# CANdiy-Shield_v12.net
KiCad netlist of a schematic drawn in EAGLE
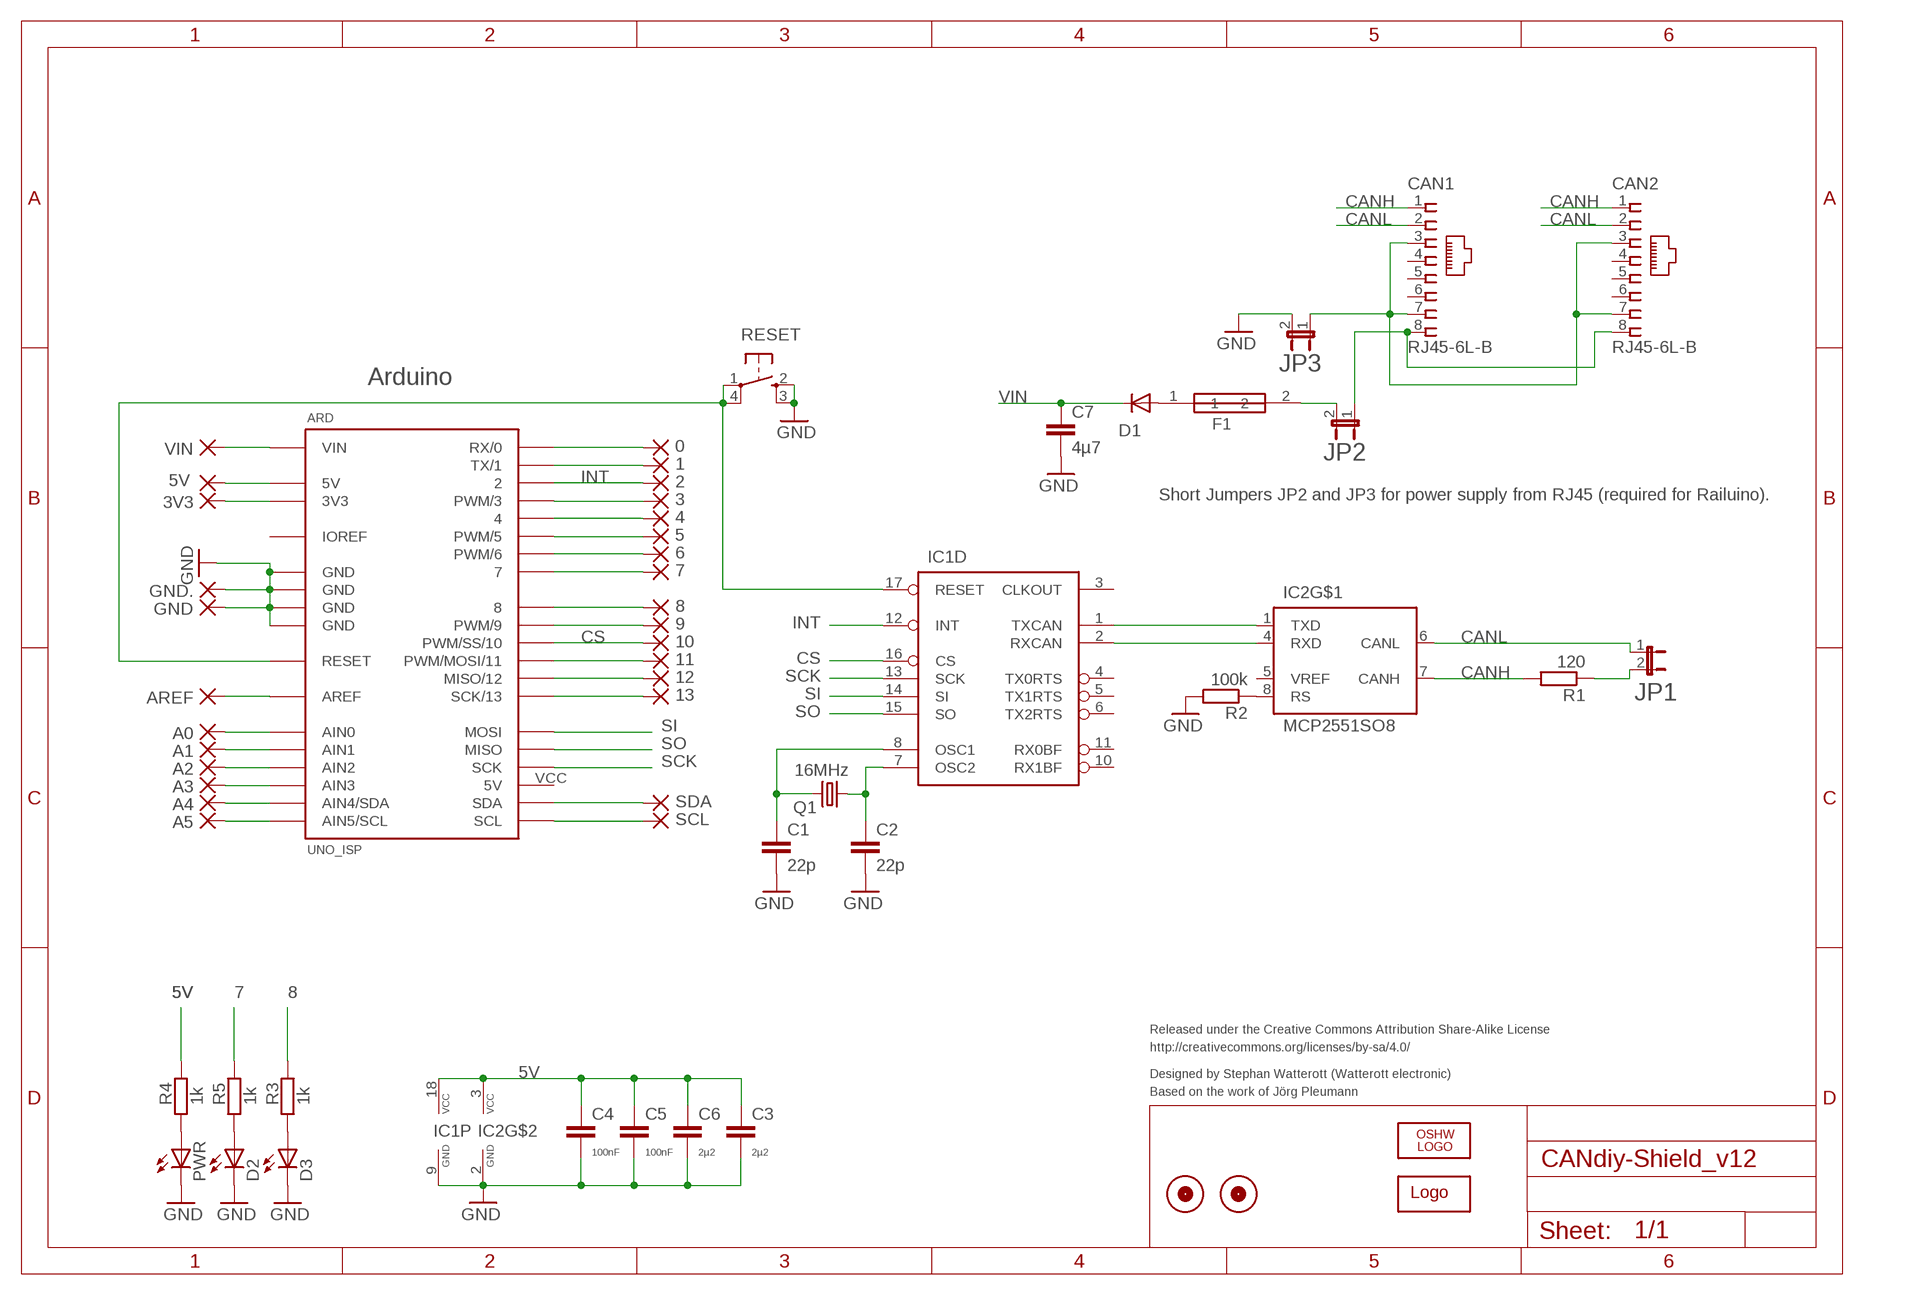
[diagram p0: schematic, sheet 1]

(export (version "E")
  (design (tool "Eeschema 10.0.6"))
  (components
    (comp (ref "0")
      (value "1,6/0,8")
      (footprint "eagle-import:1,6_0,8")
      (libsource (lib "eagle-import") (part "1,6/0,8"))
    )
    (comp (ref "1")
      (value "1,6/0,8")
      (footprint "eagle-import:1,6_0,8")
      (libsource (lib "eagle-import") (part "1,6/0,8"))
    )
    (comp (ref "2")
      (value "1,6/0,8")
      (footprint "eagle-import:1,6_0,8")
      (libsource (lib "eagle-import") (part "1,6/0,8"))
    )
    (comp (ref "3")
      (value "1,6/0,8")
      (footprint "eagle-import:1,6_0,8")
      (libsource (lib "eagle-import") (part "1,6/0,8"))
    )
    (comp (ref "3V3")
      (value "1,6/0,8")
      (footprint "eagle-import:1,6_0,8")
      (libsource (lib "eagle-import") (part "1,6/0,8"))
    )
    (comp (ref "4")
      (value "1,6/0,8")
      (footprint "eagle-import:1,6_0,8")
      (libsource (lib "eagle-import") (part "1,6/0,8"))
    )
    (comp (ref "5")
      (value "1,6/0,8")
      (footprint "eagle-import:1,6_0,8")
      (libsource (lib "eagle-import") (part "1,6/0,8"))
    )
    (comp (ref "5V")
      (value "1,6/0,8")
      (footprint "eagle-import:1,6_0,8")
      (libsource (lib "eagle-import") (part "1,6/0,8"))
    )
    (comp (ref "6")
      (value "1,6/0,8")
      (footprint "eagle-import:1,6_0,8")
      (libsource (lib "eagle-import") (part "1,6/0,8"))
    )
    (comp (ref "7")
      (value "1,6/0,8")
      (footprint "eagle-import:1,6_0,8")
      (libsource (lib "eagle-import") (part "1,6/0,8"))
    )
    (comp (ref "8")
      (value "1,6/0,8")
      (footprint "eagle-import:1,6_0,8")
      (libsource (lib "eagle-import") (part "1,6/0,8"))
    )
    (comp (ref "9")
      (value "1,6/0,8")
      (footprint "eagle-import:1,6_0,8")
      (libsource (lib "eagle-import") (part "1,6/0,8"))
    )
    (comp (ref "10")
      (value "1,6/0,8")
      (footprint "eagle-import:1,6_0,8")
      (libsource (lib "eagle-import") (part "1,6/0,8"))
    )
    (comp (ref "11")
      (value "1,6/0,8")
      (footprint "eagle-import:1,6_0,8")
      (libsource (lib "eagle-import") (part "1,6/0,8"))
    )
    (comp (ref "12")
      (value "1,6/0,8")
      (footprint "eagle-import:1,6_0,8")
      (libsource (lib "eagle-import") (part "1,6/0,8"))
    )
    (comp (ref "13")
      (value "1,6/0,8")
      (footprint "eagle-import:1,6_0,8")
      (libsource (lib "eagle-import") (part "1,6/0,8"))
    )
    (comp (ref "A0")
      (value "1,6/0,8")
      (footprint "eagle-import:1,6_0,8")
      (libsource (lib "eagle-import") (part "1,6/0,8"))
    )
    (comp (ref "A1")
      (value "1,6/0,8")
      (footprint "eagle-import:1,6_0,8")
      (libsource (lib "eagle-import") (part "1,6/0,8"))
    )
    (comp (ref "A2")
      (value "1,6/0,8")
      (footprint "eagle-import:1,6_0,8")
      (libsource (lib "eagle-import") (part "1,6/0,8"))
    )
    (comp (ref "A3")
      (value "1,6/0,8")
      (footprint "eagle-import:1,6_0,8")
      (libsource (lib "eagle-import") (part "1,6/0,8"))
    )
    (comp (ref "A4")
      (value "1,6/0,8")
      (footprint "eagle-import:1,6_0,8")
      (libsource (lib "eagle-import") (part "1,6/0,8"))
    )
    (comp (ref "A5")
      (value "1,6/0,8")
      (footprint "eagle-import:1,6_0,8")
      (libsource (lib "eagle-import") (part "1,6/0,8"))
    )
    (comp (ref "ARD")
      (value "UNO_ISP")
      (footprint "eagle-import:UNO_ISP")
      (libsource (lib "eagle-import") (part "UNO_ISP"))
    )
    (comp (ref "AREF")
      (value "1,6/0,8")
      (footprint "eagle-import:1,6_0,8")
      (libsource (lib "eagle-import") (part "1,6/0,8"))
    )
    (comp (ref "C1")
      (value "22p")
      (footprint "eagle-import:C0603")
      (libsource (lib "eagle-import") (part "C-EUC0603"))
    )
    (comp (ref "C2")
      (value "22p")
      (footprint "eagle-import:C0603")
      (libsource (lib "eagle-import") (part "C-EUC0603"))
    )
    (comp (ref "C3")
      (value "2µ2")
      (footprint "eagle-import:C0603")
      (libsource (lib "eagle-import") (part "C-EUC0603"))
    )
    (comp (ref "C4")
      (value "100nF")
      (footprint "eagle-import:C0603")
      (libsource (lib "eagle-import") (part "C-EUC0603"))
    )
    (comp (ref "C5")
      (value "100nF")
      (footprint "eagle-import:C0603")
      (libsource (lib "eagle-import") (part "C-EUC0603"))
    )
    (comp (ref "C6")
      (value "2µ2")
      (footprint "eagle-import:C0603")
      (libsource (lib "eagle-import") (part "C-EUC0603"))
    )
    (comp (ref "C7")
      (value "4µ7")
      (footprint "eagle-import:C1206")
      (libsource (lib "eagle-import") (part "C-EUC1206"))
    )
    (comp (ref "CAN1")
      (value "RJ45-6L-B")
      (footprint "eagle-import:RJ45-NO-SHIELD")
      (libsource (lib "eagle-import") (part "RJ45-6L-B"))
    )
    (comp (ref "CAN2")
      (value "RJ45-6L-B")
      (footprint "eagle-import:RJ45-NO-SHIELD")
      (libsource (lib "eagle-import") (part "RJ45-6L-B"))
    )
    (comp (ref "D1")
      (value "CGRM4001-G")
      (footprint "eagle-import:SOD-123_MINI-SMA")
      (libsource (lib "eagle-import") (part "CGRM400-G1"))
    )
    (comp (ref "D2")
      (value "LEDCHIPLED_0603")
      (footprint "eagle-import:CHIPLED_0603")
      (libsource (lib "eagle-import") (part "LEDCHIPLED_0603"))
    )
    (comp (ref "D3")
      (value "LEDCHIPLED_0603")
      (footprint "eagle-import:CHIPLED_0603")
      (libsource (lib "eagle-import") (part "LEDCHIPLED_0603"))
    )
    (comp (ref "F1")
      (value "F1")
      (footprint "eagle-import:L1812")
      (libsource (lib "eagle-import") (part "FUSE1812"))
    )
    (comp (ref "GND")
      (value "1,6/0,8")
      (footprint "eagle-import:1,6_0,8")
      (libsource (lib "eagle-import") (part "1,6/0,8"))
    )
    (comp (ref "GND.")
      (value "1,6/0,8")
      (footprint "eagle-import:1,6_0,8")
      (libsource (lib "eagle-import") (part "1,6/0,8"))
    )
    (comp (ref "IC1")
      (value "MCP2515SO")
      (footprint "eagle-import:SO-18W")
      (libsource (lib "eagle-import") (part "MCP2515SO"))
    )
    (comp (ref "IC2")
      (value "MCP2551SO8")
      (footprint "eagle-import:SO08")
      (libsource (lib "eagle-import") (part "MCP2551SO8"))
    )
    (comp (ref "JP1")
      (value "JP1E")
      (footprint "eagle-import:JP1")
      (libsource (lib "eagle-import") (part "JP1E"))
    )
    (comp (ref "JP2")
      (value "JP1E")
      (footprint "eagle-import:JP1")
      (libsource (lib "eagle-import") (part "JP1E"))
    )
    (comp (ref "JP3")
      (value "JP1E")
      (footprint "eagle-import:JP1")
      (libsource (lib "eagle-import") (part "JP1E"))
    )
    (comp (ref "LOGO2")
      (value "OSHW_LOGO_6MILX0100-NT")
      (footprint "eagle-import:OSHW_6X100_NOTEXT")
      (libsource (lib "eagle-import") (part "OSHW_LOGO_6MILX0100-NT"))
    )
    (comp (ref "PWR")
      (value "LEDCHIPLED_0603")
      (footprint "eagle-import:CHIPLED_0603")
      (libsource (lib "eagle-import") (part "LEDCHIPLED_0603"))
    )
    (comp (ref "Q1")
      (value "16MHz")
      (footprint "eagle-import:HC49UP")
      (libsource (lib "eagle-import") (part "CRYSTALHC49UP"))
    )
    (comp (ref "R1")
      (value "120")
      (footprint "eagle-import:R0603")
      (libsource (lib "eagle-import") (part "resistor_R-EU_R0603"))
    )
    (comp (ref "R2")
      (value "100k")
      (footprint "eagle-import:R0603")
      (libsource (lib "eagle-import") (part "resistor_R-EU_R0603"))
    )
    (comp (ref "R3")
      (value "1k")
      (footprint "eagle-import:R0603")
      (libsource (lib "eagle-import") (part "R-EU_R0603"))
    )
    (comp (ref "R4")
      (value "1k")
      (footprint "eagle-import:R0603")
      (libsource (lib "eagle-import") (part "R-EU_R0603"))
    )
    (comp (ref "R5")
      (value "1k")
      (footprint "eagle-import:R0603")
      (libsource (lib "eagle-import") (part "R-EU_R0603"))
    )
    (comp (ref "RESET")
      (value "SW_SMDS")
      (footprint "eagle-import:SW_SMD4")
      (libsource (lib "eagle-import") (part "SW_SMDS"))
    )
    (comp (ref "SCL")
      (value "1,6/0,8")
      (footprint "eagle-import:1,6_0,8")
      (libsource (lib "eagle-import") (part "1,6/0,8"))
    )
    (comp (ref "SDA")
      (value "1,6/0,8")
      (footprint "eagle-import:1,6_0,8")
      (libsource (lib "eagle-import") (part "1,6/0,8"))
    )
    (comp (ref "U$1")
      (value "WE-LOGO")
      (footprint "eagle-import:WE-LOGO")
      (libsource (lib "eagle-import") (part "WE-LOGO"))
    )
    (comp (ref "VIN")
      (value "1,6/0,8")
      (footprint "eagle-import:1,6_0,8")
      (libsource (lib "eagle-import") (part "1,6/0,8"))
    )
    (comp (ref "X_1")
      (value "PASS_1MM")
      (footprint "eagle-import:ROUND_1MM")
      (libsource (lib "eagle-import") (part "PASS_1MM"))
    )
    (comp (ref "X_2")
      (value "PASS_1MM")
      (footprint "eagle-import:ROUND_1MM")
      (libsource (lib "eagle-import") (part "PASS_1MM"))
    )
  )
  (nets
    (net (code "1") (name "/5V") (class "Default")
      (node (ref "5V") (pin "1") (pinfunction "P_1") (pintype "passive"))
      (node (ref "ARD") (pin "5V") (pinfunction "5V_5V") (pintype "power_in"))
      (node (ref "C3") (pin "1") (pinfunction "1_1") (pintype "passive"))
      (node (ref "C4") (pin "1") (pinfunction "1_1") (pintype "passive"))
      (node (ref "C5") (pin "1") (pinfunction "1_1") (pintype "passive"))
      (node (ref "C6") (pin "1") (pinfunction "1_1") (pintype "passive"))
      (node (ref "IC1") (pin "18") (pinfunction "VCC_18") (pintype "power_in"))
      (node (ref "IC2") (pin "3") (pinfunction "VCC_3") (pintype "power_in"))
      (node (ref "R4") (pin "1") (pinfunction "1_1") (pintype "passive"))
    )
    (net (code "2") (name "/7") (class "Default")
      (node (ref "7") (pin "1") (pinfunction "P_1") (pintype "passive"))
      (node (ref "ARD") (pin "7") (pinfunction "7_7") (pintype "bidirectional"))
      (node (ref "R5") (pin "1") (pinfunction "1_1") (pintype "passive"))
    )
    (net (code "3") (name "/8") (class "Default")
      (node (ref "8") (pin "1") (pinfunction "P_1") (pintype "passive"))
      (node (ref "ARD") (pin "8") (pinfunction "8_8") (pintype "bidirectional"))
      (node (ref "R3") (pin "1") (pinfunction "1_1") (pintype "passive"))
    )
    (net (code "4") (name "/CANH") (class "Default")
      (node (ref "CAN1") (pin "1") (pinfunction "1_1") (pintype "passive"))
      (node (ref "CAN2") (pin "1") (pinfunction "1_1") (pintype "passive"))
      (node (ref "IC2") (pin "7") (pinfunction "CANH_7") (pintype "bidirectional"))
      (node (ref "R1") (pin "2") (pinfunction "2_2") (pintype "passive"))
    )
    (net (code "5") (name "/CANL") (class "Default")
      (node (ref "CAN1") (pin "2") (pinfunction "2_2") (pintype "passive"))
      (node (ref "CAN2") (pin "2") (pinfunction "2_2") (pintype "passive"))
      (node (ref "IC2") (pin "6") (pinfunction "CANL_6") (pintype "bidirectional"))
      (node (ref "JP1") (pin "1") (pinfunction "1_1") (pintype "passive"))
    )
    (net (code "6") (name "/CS") (class "Default")
      (node (ref "10") (pin "1") (pinfunction "P_1") (pintype "passive"))
      (node (ref "ARD") (pin "10") (pinfunction "PWM/SS/10_10") (pintype "bidirectional"))
      (node (ref "IC1") (pin "16") (pinfunction "CS_16") (pintype "input"))
    )
    (net (code "7") (name "/INT") (class "Default")
      (node (ref "2") (pin "1") (pinfunction "P_1") (pintype "passive"))
      (node (ref "ARD") (pin "2") (pinfunction "2_2") (pintype "bidirectional"))
      (node (ref "IC1") (pin "12") (pinfunction "INT_12") (pintype "output"))
    )
    (net (code "8") (name "/IOREF") (class "Default")
      (node (ref "ARD") (pin "IOREF") (pinfunction "IOREF_IOREF") (pintype "power_in"))
    )
    (net (code "9") (name "/SCK") (class "Default")
      (node (ref "ARD") (pin "SCK") (pinfunction "SCK_SCK") (pintype "bidirectional"))
      (node (ref "IC1") (pin "13") (pinfunction "SCK_13") (pintype "input"))
    )
    (net (code "10") (name "/SI") (class "Default")
      (node (ref "ARD") (pin "MOSI") (pinfunction "MOSI_MOSI") (pintype "bidirectional"))
      (node (ref "IC1") (pin "14") (pinfunction "SI_14") (pintype "input"))
    )
    (net (code "11") (name "/SO") (class "Default")
      (node (ref "ARD") (pin "MISO") (pinfunction "MISO_MISO") (pintype "bidirectional"))
      (node (ref "IC1") (pin "15") (pinfunction "SO_15") (pintype "output"))
    )
    (net (code "12") (name "/VIN") (class "Default")
      (node (ref "ARD") (pin "VIN") (pinfunction "VIN_VIN") (pintype "power_in"))
      (node (ref "C7") (pin "1") (pinfunction "1_1") (pintype "passive"))
      (node (ref "D1") (pin "C") (pinfunction "C_C") (pintype "passive"))
      (node (ref "VIN") (pin "1") (pinfunction "P_1") (pintype "passive"))
    )
    (net (code "13") (name "GND") (class "Default")
      (node (ref "ARD") (pin "GND@1") (pinfunction "GND_GND@1") (pintype "power_in"))
      (node (ref "ARD") (pin "GND@2") (pinfunction "GND_GND@2") (pintype "power_in"))
      (node (ref "ARD") (pin "GND@3") (pinfunction "GND_GND@3") (pintype "power_in"))
      (node (ref "ARD") (pin "GND@4") (pinfunction "GND_GND@4") (pintype "power_in"))
      (node (ref "C1") (pin "2") (pinfunction "2_2") (pintype "passive"))
      (node (ref "C2") (pin "2") (pinfunction "2_2") (pintype "passive"))
      (node (ref "C3") (pin "2") (pinfunction "2_2") (pintype "passive"))
      (node (ref "C4") (pin "2") (pinfunction "2_2") (pintype "passive"))
      (node (ref "C5") (pin "2") (pinfunction "2_2") (pintype "passive"))
      (node (ref "C6") (pin "2") (pinfunction "2_2") (pintype "passive"))
      (node (ref "C7") (pin "2") (pinfunction "2_2") (pintype "passive"))
      (node (ref "D2") (pin "C") (pinfunction "C_C") (pintype "passive"))
      (node (ref "D3") (pin "C") (pinfunction "C_C") (pintype "passive"))
      (node (ref "GND") (pin "1") (pinfunction "P_1") (pintype "passive"))
      (node (ref "GND.") (pin "1") (pinfunction "P_1") (pintype "passive"))
      (node (ref "IC1") (pin "9") (pinfunction "GND_9") (pintype "power_in"))
      (node (ref "IC2") (pin "2") (pinfunction "GND_2") (pintype "power_in"))
      (node (ref "JP3") (pin "2") (pinfunction "2_2") (pintype "passive"))
      (node (ref "PWR") (pin "C") (pinfunction "C_C") (pintype "passive"))
      (node (ref "R2") (pin "2") (pinfunction "2_2") (pintype "passive"))
      (node (ref "RESET") (pin "2") (pinfunction "S_2") (pintype "passive"))
      (node (ref "RESET") (pin "3") (pinfunction "S1_3") (pintype "passive"))
    )
    (net (code "14") (name "Net-(0-P)") (class "Default")
      (node (ref "0") (pin "1") (pinfunction "P_1") (pintype "passive"))
      (node (ref "ARD") (pin "0") (pinfunction "RX/0_0") (pintype "bidirectional"))
    )
    (net (code "15") (name "Net-(1-P)") (class "Default")
      (node (ref "1") (pin "1") (pinfunction "P_1") (pintype "passive"))
      (node (ref "ARD") (pin "1") (pinfunction "TX/1_1") (pintype "bidirectional"))
    )
    (net (code "16") (name "Net-(3-P)") (class "Default")
      (node (ref "3") (pin "1") (pinfunction "P_1") (pintype "passive"))
      (node (ref "ARD") (pin "3") (pinfunction "PWM/3_3") (pintype "bidirectional"))
    )
    (net (code "17") (name "Net-(3V3-P)") (class "Default")
      (node (ref "3V3") (pin "1") (pinfunction "P_1") (pintype "passive"))
      (node (ref "ARD") (pin "3V3") (pinfunction "3V3_3V3") (pintype "power_in"))
    )
    (net (code "18") (name "Net-(4-P)") (class "Default")
      (node (ref "4") (pin "1") (pinfunction "P_1") (pintype "passive"))
      (node (ref "ARD") (pin "4") (pinfunction "4_4") (pintype "bidirectional"))
    )
    (net (code "19") (name "Net-(5-P)") (class "Default")
      (node (ref "5") (pin "1") (pinfunction "P_1") (pintype "passive"))
      (node (ref "ARD") (pin "5") (pinfunction "PWM/5_5") (pintype "bidirectional"))
    )
    (net (code "20") (name "Net-(6-P)") (class "Default")
      (node (ref "6") (pin "1") (pinfunction "P_1") (pintype "passive"))
      (node (ref "ARD") (pin "6") (pinfunction "PWM/6_6") (pintype "bidirectional"))
    )
    (net (code "21") (name "Net-(9-P)") (class "Default")
      (node (ref "9") (pin "1") (pinfunction "P_1") (pintype "passive"))
      (node (ref "ARD") (pin "9") (pinfunction "PWM/9_9") (pintype "bidirectional"))
    )
    (net (code "22") (name "Net-(11-P)") (class "Default")
      (node (ref "11") (pin "1") (pinfunction "P_1") (pintype "passive"))
      (node (ref "ARD") (pin "11") (pinfunction "PWM/MOSI/11_11") (pintype "bidirectional"))
    )
    (net (code "23") (name "Net-(12-P)") (class "Default")
      (node (ref "12") (pin "1") (pinfunction "P_1") (pintype "passive"))
      (node (ref "ARD") (pin "12") (pinfunction "MISO/12_12") (pintype "bidirectional"))
    )
    (net (code "24") (name "Net-(13-P)") (class "Default")
      (node (ref "13") (pin "1") (pinfunction "P_1") (pintype "passive"))
      (node (ref "ARD") (pin "13") (pinfunction "SCK/13_13") (pintype "bidirectional"))
    )
    (net (code "25") (name "Net-(A0-P)") (class "Default")
      (node (ref "A0") (pin "1") (pinfunction "P_1") (pintype "passive"))
      (node (ref "ARD") (pin "AIN0") (pinfunction "AIN0_AIN0") (pintype "bidirectional"))
    )
    (net (code "26") (name "Net-(A1-P)") (class "Default")
      (node (ref "A1") (pin "1") (pinfunction "P_1") (pintype "passive"))
      (node (ref "ARD") (pin "AIN1") (pinfunction "AIN1_AIN1") (pintype "bidirectional"))
    )
    (net (code "27") (name "Net-(A2-P)") (class "Default")
      (node (ref "A2") (pin "1") (pinfunction "P_1") (pintype "passive"))
      (node (ref "ARD") (pin "AIN2") (pinfunction "AIN2_AIN2") (pintype "bidirectional"))
    )
    (net (code "28") (name "Net-(A3-P)") (class "Default")
      (node (ref "A3") (pin "1") (pinfunction "P_1") (pintype "passive"))
      (node (ref "ARD") (pin "AIN3") (pinfunction "AIN3_AIN3") (pintype "bidirectional"))
    )
    (net (code "29") (name "Net-(A4-P)") (class "Default")
      (node (ref "A4") (pin "1") (pinfunction "P_1") (pintype "passive"))
      (node (ref "ARD") (pin "AIN4") (pinfunction "AIN4/SDA_AIN4") (pintype "bidirectional"))
    )
    (net (code "30") (name "Net-(A5-P)") (class "Default")
      (node (ref "A5") (pin "1") (pinfunction "P_1") (pintype "passive"))
      (node (ref "ARD") (pin "AIN5") (pinfunction "AIN5/SCL_AIN5") (pintype "bidirectional"))
    )
    (net (code "31") (name "Net-(ARD-RESET)") (class "Default")
      (node (ref "ARD") (pin "RST") (pinfunction "RESET_RST") (pintype "bidirectional"))
      (node (ref "IC1") (pin "17") (pinfunction "RESET_17") (pintype "input"))
      (node (ref "RESET") (pin "1") (pinfunction "P_1") (pintype "passive"))
      (node (ref "RESET") (pin "4") (pinfunction "P1_4") (pintype "passive"))
    )
    (net (code "32") (name "Net-(AREF-P)") (class "Default")
      (node (ref "ARD") (pin "AREF") (pinfunction "AREF_AREF") (pintype "power_in"))
      (node (ref "AREF") (pin "1") (pinfunction "P_1") (pintype "passive"))
    )
    (net (code "33") (name "Net-(CAN1-Pad3)") (class "Default")
      (node (ref "CAN1") (pin "3") (pinfunction "3_3") (pintype "passive"))
      (node (ref "CAN1") (pin "7") (pinfunction "7_7") (pintype "passive"))
      (node (ref "CAN2") (pin "3") (pinfunction "3_3") (pintype "passive"))
      (node (ref "CAN2") (pin "7") (pinfunction "7_7") (pintype "passive"))
      (node (ref "JP3") (pin "1") (pinfunction "1_1") (pintype "passive"))
    )
    (net (code "34") (name "Net-(CAN1-Pad8)") (class "Default")
      (node (ref "CAN1") (pin "8") (pinfunction "8_8") (pintype "passive"))
      (node (ref "CAN2") (pin "8") (pinfunction "8_8") (pintype "passive"))
      (node (ref "JP2") (pin "1") (pinfunction "1_1") (pintype "passive"))
    )
    (net (code "35") (name "Net-(D1-PadA)") (class "Default")
      (node (ref "D1") (pin "A") (pinfunction "A_A") (pintype "passive"))
      (node (ref "F1") (pin "1") (pinfunction "1_1") (pintype "bidirectional"))
    )
    (net (code "36") (name "Net-(D2-PadA)") (class "Default")
      (node (ref "D2") (pin "A") (pinfunction "A_A") (pintype "passive"))
      (node (ref "R5") (pin "2") (pinfunction "2_2") (pintype "passive"))
    )
    (net (code "37") (name "Net-(D3-PadA)") (class "Default")
      (node (ref "D3") (pin "A") (pinfunction "A_A") (pintype "passive"))
      (node (ref "R3") (pin "2") (pinfunction "2_2") (pintype "passive"))
    )
    (net (code "38") (name "Net-(F1-Pad2)") (class "Default")
      (node (ref "F1") (pin "2") (pinfunction "2_2") (pintype "bidirectional"))
      (node (ref "JP2") (pin "2") (pinfunction "2_2") (pintype "passive"))
    )
    (net (code "39") (name "Net-(IC1A-OSC1)") (class "Default")
      (node (ref "C1") (pin "1") (pinfunction "1_1") (pintype "passive"))
      (node (ref "IC1") (pin "8") (pinfunction "OSC1_8") (pintype "input"))
      (node (ref "Q1") (pin "2") (pinfunction "2_2") (pintype "passive"))
    )
    (net (code "40") (name "Net-(IC1A-OSC2)") (class "Default")
      (node (ref "C2") (pin "1") (pinfunction "1_1") (pintype "passive"))
      (node (ref "IC1") (pin "7") (pinfunction "OSC2_7") (pintype "input"))
      (node (ref "Q1") (pin "1") (pinfunction "1_1") (pintype "passive"))
    )
    (net (code "41") (name "Net-(IC1A-RXCAN)") (class "Default")
      (node (ref "IC1") (pin "2") (pinfunction "RXCAN_2") (pintype "input"))
      (node (ref "IC2") (pin "4") (pinfunction "RXD_4") (pintype "bidirectional"))
    )
    (net (code "42") (name "Net-(IC1A-TXCAN)") (class "Default")
      (node (ref "IC1") (pin "1") (pinfunction "TXCAN_1") (pintype "output"))
      (node (ref "IC2") (pin "1") (pinfunction "TXD_1") (pintype "bidirectional"))
    )
    (net (code "43") (name "Net-(IC2A-RS)") (class "Default")
      (node (ref "IC2") (pin "8") (pinfunction "RS_8") (pintype "bidirectional"))
      (node (ref "R2") (pin "1") (pinfunction "1_1") (pintype "passive"))
    )
    (net (code "44") (name "Net-(JP1-Pad2)") (class "Default")
      (node (ref "JP1") (pin "2") (pinfunction "2_2") (pintype "passive"))
      (node (ref "R1") (pin "1") (pinfunction "1_1") (pintype "passive"))
    )
    (net (code "45") (name "Net-(PWR-PadA)") (class "Default")
      (node (ref "PWR") (pin "A") (pinfunction "A_A") (pintype "passive"))
      (node (ref "R4") (pin "2") (pinfunction "2_2") (pintype "passive"))
    )
    (net (code "46") (name "Net-(SCL-P)") (class "Default")
      (node (ref "ARD") (pin "SCL") (pinfunction "SCL_SCL") (pintype "bidirectional"))
      (node (ref "SCL") (pin "1") (pinfunction "P_1") (pintype "passive"))
    )
    (net (code "47") (name "Net-(SDA-P)") (class "Default")
      (node (ref "ARD") (pin "SDA") (pinfunction "SDA_SDA") (pintype "bidirectional"))
      (node (ref "SDA") (pin "1") (pinfunction "P_1") (pintype "passive"))
    )
    (net (code "48") (name "unconnected-(ARD-5V-PadVCC)") (class "Default")
      (node (ref "ARD") (pin "VCC") (pinfunction "5V_VCC") (pintype "bidirectional"))
    )
    (net (code "49") (name "unconnected-(CAN1-Pad4)") (class "Default")
      (node (ref "CAN1") (pin "4") (pinfunction "4_4") (pintype "passive"))
    )
    (net (code "50") (name "unconnected-(CAN1-Pad5)") (class "Default")
      (node (ref "CAN1") (pin "5") (pinfunction "5_5") (pintype "passive"))
    )
    (net (code "51") (name "unconnected-(CAN1-Pad6)") (class "Default")
      (node (ref "CAN1") (pin "6") (pinfunction "6_6") (pintype "passive"))
    )
    (net (code "52") (name "unconnected-(CAN2-Pad4)") (class "Default")
      (node (ref "CAN2") (pin "4") (pinfunction "4_4") (pintype "passive"))
    )
    (net (code "53") (name "unconnected-(CAN2-Pad5)") (class "Default")
      (node (ref "CAN2") (pin "5") (pinfunction "5_5") (pintype "passive"))
    )
    (net (code "54") (name "unconnected-(CAN2-Pad6)") (class "Default")
      (node (ref "CAN2") (pin "6") (pinfunction "6_6") (pintype "passive"))
    )
    (net (code "55") (name "unconnected-(IC1A-CLKOUT-Pad3)") (class "Default")
      (node (ref "IC1") (pin "3") (pinfunction "CLKOUT_3") (pintype "output"))
    )
    (net (code "56") (name "unconnected-(IC1A-RX0BF-Pad11)") (class "Default")
      (node (ref "IC1") (pin "11") (pinfunction "RX0BF_11") (pintype "output"))
    )
    (net (code "57") (name "unconnected-(IC1A-RX1BF-Pad10)") (class "Default")
      (node (ref "IC1") (pin "10") (pinfunction "RX1BF_10") (pintype "output"))
    )
    (net (code "58") (name "unconnected-(IC1A-TX0RTS-Pad4)") (class "Default")
      (node (ref "IC1") (pin "4") (pinfunction "TX0RTS_4") (pintype "input"))
    )
    (net (code "59") (name "unconnected-(IC1A-TX1RTS-Pad5)") (class "Default")
      (node (ref "IC1") (pin "5") (pinfunction "TX1RTS_5") (pintype "input"))
    )
    (net (code "60") (name "unconnected-(IC1A-TX2RTS-Pad6)") (class "Default")
      (node (ref "IC1") (pin "6") (pinfunction "TX2RTS_6") (pintype "input"))
    )
    (net (code "61") (name "unconnected-(IC2A-VREF-Pad5)") (class "Default")
      (node (ref "IC2") (pin "5") (pinfunction "VREF_5") (pintype "bidirectional"))
    )
  )
)
